# doorwatchV2.net
KiCad netlist of a schematic drawn in EAGLE
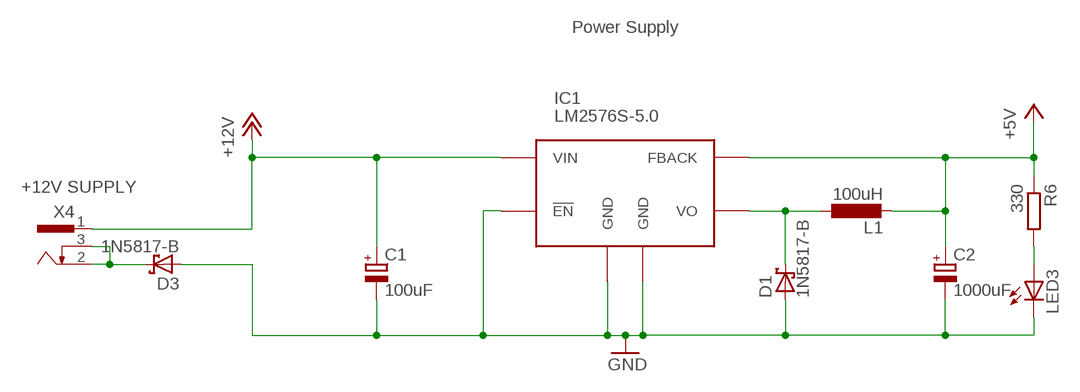
[diagram p0: schematic, sheet 1]
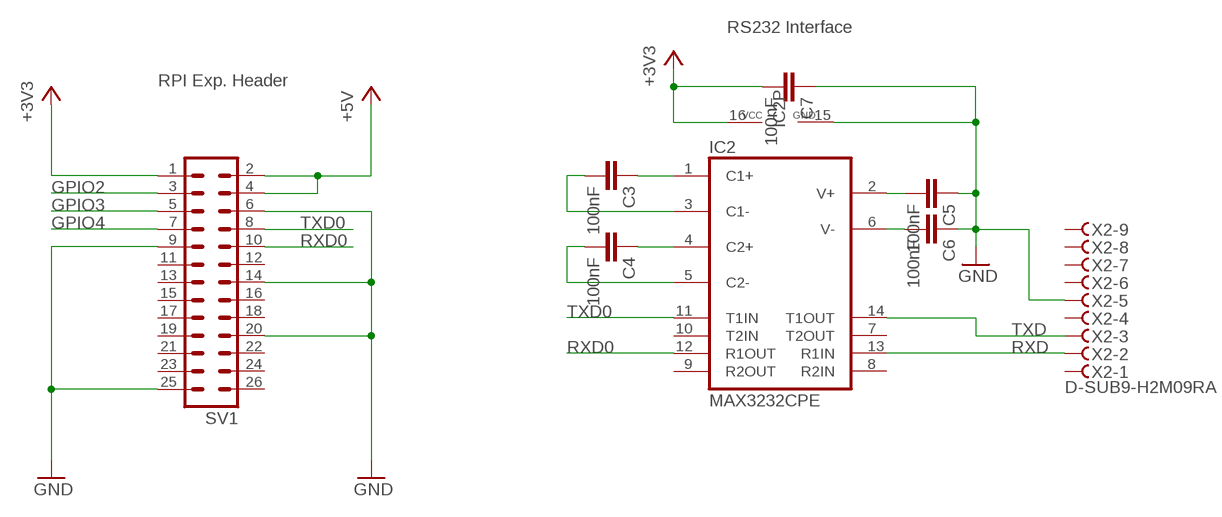
[diagram p1: schematic, sheet 2]
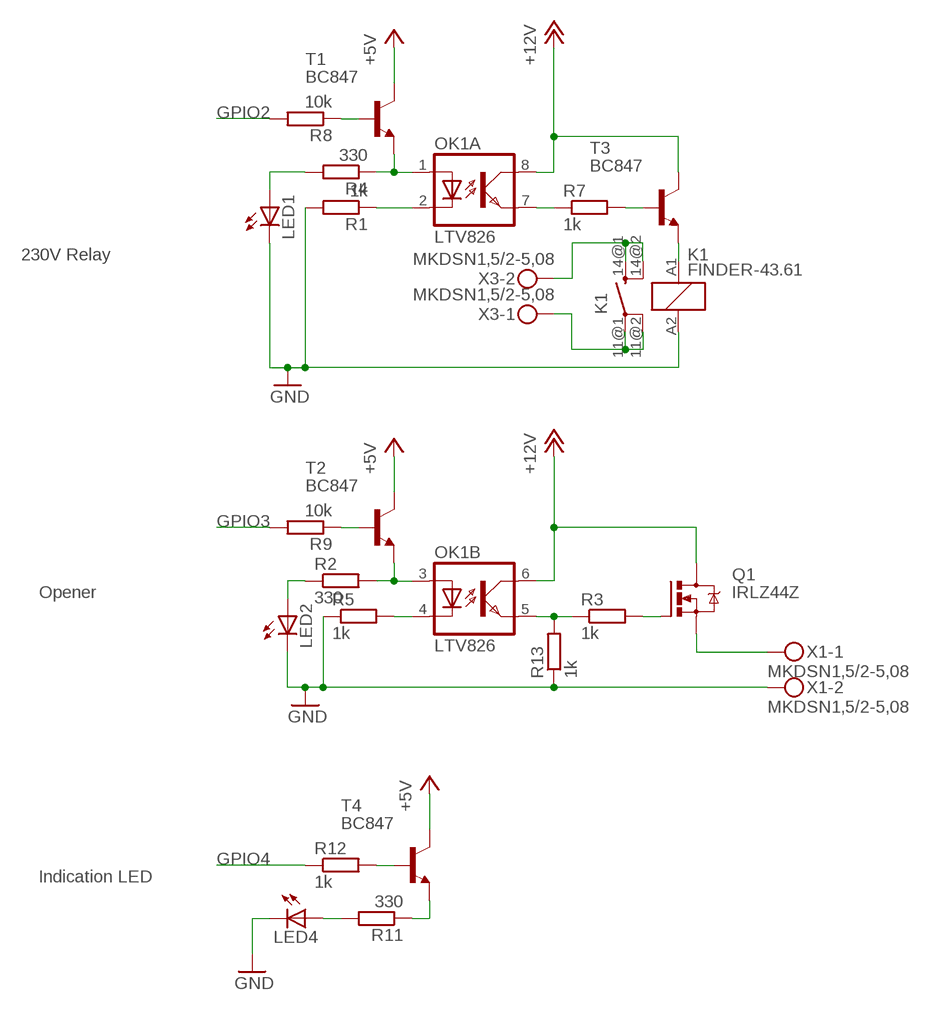
[diagram p2: schematic, sheet 3]
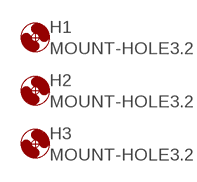
[diagram p3: schematic, sheet 4]

(export (version "E")
  (design (tool "Eeschema 10.0.6"))
  (components
    (comp (ref "H1")
      (value "MOUNT-HOLE3.2")
      (footprint "eagle-import:3,2")
      (libsource (lib "eagle-import") (part "MOUNT-HOLE3.2"))
    )
    (comp (ref "H2")
      (value "MOUNT-HOLE3.2")
      (footprint "eagle-import:3,2")
      (libsource (lib "eagle-import") (part "MOUNT-HOLE3.2"))
    )
    (comp (ref "H3")
      (value "MOUNT-HOLE3.2")
      (footprint "eagle-import:3,2")
      (libsource (lib "eagle-import") (part "MOUNT-HOLE3.2"))
    )
    (comp (ref "C1")
      (value "100uF")
      (footprint "eagle-import:E2,5-7")
      (libsource (lib "eagle-import") (part "CPOL-EUE2.5-7"))
    )
    (comp (ref "C2")
      (value "1000uF")
      (footprint "eagle-import:E5-10,5")
      (libsource (lib "eagle-import") (part "CPOL-EUE5-10.5"))
    )
    (comp (ref "D1")
      (value "1N5817-B")
      (footprint "eagle-import:DO41-7.6")
      (libsource (lib "eagle-import") (part "1N5817-B"))
    )
    (comp (ref "D3")
      (value "1N5817-B")
      (footprint "eagle-import:DO41-7.6")
      (libsource (lib "eagle-import") (part "1N5817-B"))
    )
    (comp (ref "IC1")
      (value "LM2576S-5.0")
      (footprint "eagle-import:TO263-5")
      (libsource (lib "eagle-import") (part "LM2576S"))
    )
    (comp (ref "L1")
      (value "100uH")
      (footprint "eagle-import:2200-20.32")
      (libsource (lib "eagle-import") (part "L-EU2200-20.32"))
    )
    (comp (ref "LED3")
      (value "LEDCHIP-LED0805")
      (footprint "eagle-import:CHIP-LED0805")
      (libsource (lib "eagle-import") (part "LEDCHIP-LED0805"))
    )
    (comp (ref "R6")
      (value "330")
      (footprint "eagle-import:M0805")
      (libsource (lib "eagle-import") (part "R-EU_M0805"))
    )
    (comp (ref "X4")
      (value "733980-62")
      (footprint "eagle-import:733980-62")
      (libsource (lib "eagle-import") (part "73398?0-62"))
    )
    (comp (ref "C3")
      (value "100nF")
      (footprint "eagle-import:C0805")
      (libsource (lib "eagle-import") (part "C-EUC0805"))
    )
    (comp (ref "C4")
      (value "100nF")
      (footprint "eagle-import:C0805")
      (libsource (lib "eagle-import") (part "C-EUC0805"))
    )
    (comp (ref "C5")
      (value "100nF")
      (footprint "eagle-import:C0805")
      (libsource (lib "eagle-import") (part "C-EUC0805"))
    )
    (comp (ref "C6")
      (value "100nF")
      (footprint "eagle-import:C0805")
      (libsource (lib "eagle-import") (part "C-EUC0805"))
    )
    (comp (ref "C7")
      (value "100nF")
      (footprint "eagle-import:C0805")
      (libsource (lib "eagle-import") (part "C-EUC0805"))
    )
    (comp (ref "IC2")
      (value "MAX3232CPE")
      (footprint "eagle-import:DIL16")
      (fields (field (name "MF") "MAXIM") (field (name "MPN") "MAX3232CPE+"))
      (libsource (lib "eagle-import") (part "MAX3232PEC"))
    )
    (comp (ref "SV1")
      (value "ML26")
      (footprint "eagle-import:ML26")
      (libsource (lib "eagle-import") (part "ML26"))
    )
    (comp (ref "X2")
      (value "D-SUB9-H2M09RA")
      (footprint "eagle-import:H2M09RA")
      (libsource (lib "eagle-import") (part "D-SUB9-H2M09RA"))
    )
    (comp (ref "K1")
      (value "FINDER-43.61")
      (footprint "eagle-import:FINDER-43.61")
      (libsource (lib "eagle-import") (part "FINDER-43.61"))
    )
    (comp (ref "LED1")
      (value "LEDCHIP-LED0805")
      (footprint "eagle-import:CHIP-LED0805")
      (libsource (lib "eagle-import") (part "LEDCHIP-LED0805"))
    )
    (comp (ref "LED2")
      (value "LEDCHIP-LED0805")
      (footprint "eagle-import:CHIP-LED0805")
      (libsource (lib "eagle-import") (part "LEDCHIP-LED0805"))
    )
    (comp (ref "LED4")
      (value "LEDCHIP-LED0805")
      (footprint "eagle-import:CHIP-LED0805")
      (libsource (lib "eagle-import") (part "LEDCHIP-LED0805"))
    )
    (comp (ref "OK1")
      (value "LTV826")
      (footprint "eagle-import:DIL08")
      (libsource (lib "eagle-import") (part "LTV826"))
    )
    (comp (ref "Q1")
      (value "IRLZ44Z")
      (footprint "eagle-import:TO220BH")
      (libsource (lib "eagle-import") (part "IRLZ44Z"))
    )
    (comp (ref "R1")
      (value "1k")
      (footprint "eagle-import:M0805")
      (libsource (lib "eagle-import") (part "R-EU_M0805"))
    )
    (comp (ref "R2")
      (value "330")
      (footprint "eagle-import:M0805")
      (libsource (lib "eagle-import") (part "R-EU_M0805"))
    )
    (comp (ref "R3")
      (value "1k")
      (footprint "eagle-import:M0805")
      (libsource (lib "eagle-import") (part "R-EU_M0805"))
    )
    (comp (ref "R4")
      (value "330")
      (footprint "eagle-import:M0805")
      (libsource (lib "eagle-import") (part "R-EU_M0805"))
    )
    (comp (ref "R5")
      (value "1k")
      (footprint "eagle-import:M0805")
      (libsource (lib "eagle-import") (part "R-EU_M0805"))
    )
    (comp (ref "R7")
      (value "1k")
      (footprint "eagle-import:M0805")
      (libsource (lib "eagle-import") (part "R-EU_M0805"))
    )
    (comp (ref "R8")
      (value "10k")
      (footprint "eagle-import:M0805")
      (libsource (lib "eagle-import") (part "R-EU_M0805"))
    )
    (comp (ref "R9")
      (value "10k")
      (footprint "eagle-import:M0805")
      (libsource (lib "eagle-import") (part "R-EU_M0805"))
    )
    (comp (ref "R11")
      (value "330")
      (footprint "eagle-import:M0805")
      (libsource (lib "eagle-import") (part "R-EU_M0805"))
    )
    (comp (ref "R12")
      (value "1k")
      (footprint "eagle-import:M0805")
      (libsource (lib "eagle-import") (part "R-EU_M0805"))
    )
    (comp (ref "R13")
      (value "1k")
      (footprint "eagle-import:M0805")
      (libsource (lib "eagle-import") (part "R-EU_M0805"))
    )
    (comp (ref "T1")
      (value "BC847")
      (footprint "eagle-import:SOT23")
      (libsource (lib "eagle-import") (part "BC847"))
    )
    (comp (ref "T2")
      (value "BC847")
      (footprint "eagle-import:SOT23")
      (libsource (lib "eagle-import") (part "BC847"))
    )
    (comp (ref "T3")
      (value "BC847")
      (footprint "eagle-import:SOT23")
      (libsource (lib "eagle-import") (part "BC847"))
    )
    (comp (ref "T4")
      (value "BC847")
      (footprint "eagle-import:SOT23")
      (libsource (lib "eagle-import") (part "BC847"))
    )
    (comp (ref "X1")
      (value "MKDSN1,5/2-5,08")
      (footprint "eagle-import:MKDSN1,5_2-5,08")
      (fields (field (name "MPN") "MKDSN 1,5/2-5.08"))
      (libsource (lib "eagle-import") (part "MKDSN1,5/2-5,08"))
    )
    (comp (ref "X3")
      (value "MKDSN1,5/2-5,08")
      (footprint "eagle-import:MKDSN1,5_2-5,08")
      (fields (field (name "MPN") "MKDSN 1,5/2-5.08"))
      (libsource (lib "eagle-import") (part "MKDSN1,5/2-5,08"))
    )
  )
  (nets
    (net (code "1") (name "+3V3") (class "Default")
      (node (ref "C7") (pin "2") (pinfunction "2_2") (pintype "passive"))
      (node (ref "IC2") (pin "16") (pinfunction "VCC_16") (pintype "power_in"))
      (node (ref "SV1") (pin "1") (pinfunction "1_1") (pintype "passive"))
    )
    (net (code "2") (name "+5V") (class "Default")
      (node (ref "C2") (pin "+") (pinfunction "+_+") (pintype "passive"))
      (node (ref "IC1") (pin "4") (pinfunction "FBACK_4") (pintype "bidirectional"))
      (node (ref "L1") (pin "2") (pinfunction "2_2") (pintype "passive"))
      (node (ref "R6") (pin "1") (pinfunction "1_1") (pintype "passive"))
      (node (ref "SV1") (pin "2") (pinfunction "2_2") (pintype "passive"))
      (node (ref "SV1") (pin "4") (pinfunction "4_4") (pintype "passive"))
      (node (ref "T1") (pin "3") (pinfunction "C_3") (pintype "passive"))
      (node (ref "T2") (pin "3") (pinfunction "C_3") (pintype "passive"))
      (node (ref "T4") (pin "3") (pinfunction "C_3") (pintype "passive"))
    )
    (net (code "3") (name "+12V") (class "Default")
      (node (ref "C1") (pin "+") (pinfunction "+_+") (pintype "passive"))
      (node (ref "IC1") (pin "1") (pinfunction "VIN_1") (pintype "bidirectional"))
      (node (ref "OK1") (pin "6") (pinfunction "COL_6") (pintype "passive"))
      (node (ref "OK1") (pin "8") (pinfunction "COL_8") (pintype "passive"))
      (node (ref "Q1") (pin "D") (pinfunction "D_D") (pintype "passive"))
      (node (ref "T3") (pin "3") (pinfunction "C_3") (pintype "passive"))
      (node (ref "X4") (pin "1") (pinfunction "1_1") (pintype "passive"))
    )
    (net (code "4") (name "GND") (class "Default")
      (node (ref "C1") (pin "-") (pinfunction "-_-") (pintype "passive"))
      (node (ref "C2") (pin "-") (pinfunction "-_-") (pintype "passive"))
      (node (ref "C5") (pin "1") (pinfunction "1_1") (pintype "passive"))
      (node (ref "C6") (pin "1") (pinfunction "1_1") (pintype "passive"))
      (node (ref "C7") (pin "1") (pinfunction "1_1") (pintype "passive"))
      (node (ref "D1") (pin "A") (pinfunction "A_A") (pintype "passive"))
      (node (ref "D3") (pin "A") (pinfunction "A_A") (pintype "passive"))
      (node (ref "IC1") (pin "3") (pinfunction "GND_3") (pintype "bidirectional"))
      (node (ref "IC1") (pin "5") (pinfunction "~{EN}_5") (pintype "bidirectional"))
      (node (ref "IC1") (pin "TAB") (pinfunction "GND_TAB") (pintype "bidirectional"))
      (node (ref "IC2") (pin "15") (pinfunction "GND_15") (pintype "power_in"))
      (node (ref "K1") (pin "A2") (pinfunction "2_A2") (pintype "passive"))
      (node (ref "LED1") (pin "C") (pinfunction "C_C") (pintype "passive"))
      (node (ref "LED2") (pin "C") (pinfunction "C_C") (pintype "passive"))
      (node (ref "LED3") (pin "C") (pinfunction "C_C") (pintype "passive"))
      (node (ref "LED4") (pin "C") (pinfunction "C_C") (pintype "passive"))
      (node (ref "R1") (pin "2") (pinfunction "2_2") (pintype "passive"))
      (node (ref "R13") (pin "1") (pinfunction "1_1") (pintype "passive"))
      (node (ref "R5") (pin "1") (pinfunction "1_1") (pintype "passive"))
      (node (ref "SV1") (pin "14") (pinfunction "14_14") (pintype "passive"))
      (node (ref "SV1") (pin "20") (pinfunction "20_20") (pintype "passive"))
      (node (ref "SV1") (pin "25") (pinfunction "25_25") (pintype "passive"))
      (node (ref "SV1") (pin "6") (pinfunction "6_6") (pintype "passive"))
      (node (ref "SV1") (pin "9") (pinfunction "9_9") (pintype "passive"))
      (node (ref "X1") (pin "2") (pinfunction "KL_2") (pintype "passive"))
      (node (ref "X2") (pin "5") (pinfunction "F_5") (pintype "passive"))
    )
    (net (code "5") (name "GPIO2") (class "Default")
      (node (ref "R8") (pin "2") (pinfunction "2_2") (pintype "passive"))
      (node (ref "SV1") (pin "3") (pinfunction "3_3") (pintype "passive"))
    )
    (net (code "6") (name "GPIO3") (class "Default")
      (node (ref "R9") (pin "2") (pinfunction "2_2") (pintype "passive"))
      (node (ref "SV1") (pin "5") (pinfunction "5_5") (pintype "passive"))
    )
    (net (code "7") (name "GPIO4") (class "Default")
      (node (ref "R12") (pin "1") (pinfunction "1_1") (pintype "passive"))
      (node (ref "SV1") (pin "7") (pinfunction "7_7") (pintype "passive"))
    )
    (net (code "8") (name "Net-(D3-PadC)") (class "Default")
      (node (ref "D3") (pin "C") (pinfunction "C_C") (pintype "passive"))
      (node (ref "X4") (pin "2") (pinfunction "2_2") (pintype "passive"))
      (node (ref "X4") (pin "3") (pinfunction "3_3") (pintype "passive"))
    )
    (net (code "9") (name "Net-(IC1-VO)") (class "Default")
      (node (ref "D1") (pin "C") (pinfunction "C_C") (pintype "passive"))
      (node (ref "IC1") (pin "2") (pinfunction "VO_2") (pintype "bidirectional"))
      (node (ref "L1") (pin "1") (pinfunction "1_1") (pintype "passive"))
    )
    (net (code "10") (name "Net-(IC2A-C1+)") (class "Default")
      (node (ref "C3") (pin "1") (pinfunction "1_1") (pintype "passive"))
      (node (ref "IC2") (pin "1") (pinfunction "C1+_1") (pintype "bidirectional"))
    )
    (net (code "11") (name "Net-(IC2A-C1-)") (class "Default")
      (node (ref "C3") (pin "2") (pinfunction "2_2") (pintype "passive"))
      (node (ref "IC2") (pin "3") (pinfunction "C1-_3") (pintype "bidirectional"))
    )
    (net (code "12") (name "Net-(IC2A-C2+)") (class "Default")
      (node (ref "C4") (pin "1") (pinfunction "1_1") (pintype "passive"))
      (node (ref "IC2") (pin "4") (pinfunction "C2+_4") (pintype "bidirectional"))
    )
    (net (code "13") (name "Net-(IC2A-C2-)") (class "Default")
      (node (ref "C4") (pin "2") (pinfunction "2_2") (pintype "passive"))
      (node (ref "IC2") (pin "5") (pinfunction "C2-_5") (pintype "bidirectional"))
    )
    (net (code "14") (name "Net-(IC2A-V+)") (class "Default")
      (node (ref "C5") (pin "2") (pinfunction "2_2") (pintype "passive"))
      (node (ref "IC2") (pin "2") (pinfunction "V+_2") (pintype "bidirectional"))
    )
    (net (code "15") (name "Net-(IC2A-V-)") (class "Default")
      (node (ref "C6") (pin "2") (pinfunction "2_2") (pintype "passive"))
      (node (ref "IC2") (pin "6") (pinfunction "V-_6") (pintype "bidirectional"))
    )
    (net (code "16") (name "Net-(K1A-PA)") (class "Default")
      (node (ref "K1") (pin "11@1") (pinfunction "PA_11@1") (pintype "passive"))
      (node (ref "K1") (pin "11@2") (pinfunction "PB_11@2") (pintype "passive"))
      (node (ref "X3") (pin "1") (pinfunction "KL_1") (pintype "passive"))
    )
    (net (code "17") (name "Net-(K1A-SA)") (class "Default")
      (node (ref "K1") (pin "14@1") (pinfunction "SA_14@1") (pintype "passive"))
      (node (ref "K1") (pin "14@2") (pinfunction "SB_14@2") (pintype "passive"))
      (node (ref "X3") (pin "2") (pinfunction "KL_2") (pintype "passive"))
    )
    (net (code "18") (name "Net-(K1B-1)") (class "Default")
      (node (ref "K1") (pin "A1") (pinfunction "1_A1") (pintype "passive"))
      (node (ref "T3") (pin "2") (pinfunction "E_2") (pintype "passive"))
    )
    (net (code "19") (name "Net-(LED1-PadA)") (class "Default")
      (node (ref "LED1") (pin "A") (pinfunction "A_A") (pintype "passive"))
      (node (ref "R4") (pin "2") (pinfunction "2_2") (pintype "passive"))
    )
    (net (code "20") (name "Net-(LED2-PadA)") (class "Default")
      (node (ref "LED2") (pin "A") (pinfunction "A_A") (pintype "passive"))
      (node (ref "R2") (pin "1") (pinfunction "1_1") (pintype "passive"))
    )
    (net (code "21") (name "Net-(LED3-PadA)") (class "Default")
      (node (ref "LED3") (pin "A") (pinfunction "A_A") (pintype "passive"))
      (node (ref "R6") (pin "2") (pinfunction "2_2") (pintype "passive"))
    )
    (net (code "22") (name "Net-(LED4-PadA)") (class "Default")
      (node (ref "LED4") (pin "A") (pinfunction "A_A") (pintype "passive"))
      (node (ref "R11") (pin "2") (pinfunction "2_2") (pintype "passive"))
    )
    (net (code "23") (name "Net-(OK1A-A)") (class "Default")
      (node (ref "OK1") (pin "1") (pinfunction "A_1") (pintype "passive"))
      (node (ref "R4") (pin "1") (pinfunction "1_1") (pintype "passive"))
      (node (ref "T1") (pin "2") (pinfunction "E_2") (pintype "passive"))
    )
    (net (code "24") (name "Net-(OK1A-C)") (class "Default")
      (node (ref "OK1") (pin "2") (pinfunction "C_2") (pintype "passive"))
      (node (ref "R1") (pin "1") (pinfunction "1_1") (pintype "passive"))
    )
    (net (code "25") (name "Net-(OK1A-EMIT)") (class "Default")
      (node (ref "OK1") (pin "7") (pinfunction "EMIT_7") (pintype "passive"))
      (node (ref "R7") (pin "1") (pinfunction "1_1") (pintype "passive"))
    )
    (net (code "26") (name "Net-(OK1B-A)") (class "Default")
      (node (ref "OK1") (pin "3") (pinfunction "A_3") (pintype "passive"))
      (node (ref "R2") (pin "2") (pinfunction "2_2") (pintype "passive"))
      (node (ref "T2") (pin "2") (pinfunction "E_2") (pintype "passive"))
    )
    (net (code "27") (name "Net-(OK1B-C)") (class "Default")
      (node (ref "OK1") (pin "4") (pinfunction "C_4") (pintype "passive"))
      (node (ref "R5") (pin "2") (pinfunction "2_2") (pintype "passive"))
    )
    (net (code "28") (name "Net-(OK1B-EMIT)") (class "Default")
      (node (ref "OK1") (pin "5") (pinfunction "EMIT_5") (pintype "passive"))
      (node (ref "R13") (pin "2") (pinfunction "2_2") (pintype "passive"))
      (node (ref "R3") (pin "1") (pinfunction "1_1") (pintype "passive"))
    )
    (net (code "29") (name "Net-(Q1-PadG)") (class "Default")
      (node (ref "Q1") (pin "G") (pinfunction "G_G") (pintype "passive"))
      (node (ref "R3") (pin "2") (pinfunction "2_2") (pintype "passive"))
    )
    (net (code "30") (name "Net-(T1-B)") (class "Default")
      (node (ref "R8") (pin "1") (pinfunction "1_1") (pintype "passive"))
      (node (ref "T1") (pin "1") (pinfunction "B_1") (pintype "passive"))
    )
    (net (code "31") (name "Net-(T2-B)") (class "Default")
      (node (ref "R9") (pin "1") (pinfunction "1_1") (pintype "passive"))
      (node (ref "T2") (pin "1") (pinfunction "B_1") (pintype "passive"))
    )
    (net (code "32") (name "Net-(T3-B)") (class "Default")
      (node (ref "R7") (pin "2") (pinfunction "2_2") (pintype "passive"))
      (node (ref "T3") (pin "1") (pinfunction "B_1") (pintype "passive"))
    )
    (net (code "33") (name "Net-(T4-B)") (class "Default")
      (node (ref "R12") (pin "2") (pinfunction "2_2") (pintype "passive"))
      (node (ref "T4") (pin "1") (pinfunction "B_1") (pintype "passive"))
    )
    (net (code "34") (name "Net-(T4-E)") (class "Default")
      (node (ref "R11") (pin "1") (pinfunction "1_1") (pintype "passive"))
      (node (ref "T4") (pin "2") (pinfunction "E_2") (pintype "passive"))
    )
    (net (code "35") (name "Net-(X1A-KL)") (class "Default")
      (node (ref "Q1") (pin "S") (pinfunction "S_S") (pintype "passive"))
      (node (ref "X1") (pin "1") (pinfunction "KL_1") (pintype "passive"))
    )
    (net (code "36") (name "RXD") (class "Default")
      (node (ref "IC2") (pin "13") (pinfunction "R1IN_13") (pintype "input"))
      (node (ref "X2") (pin "2") (pinfunction "F_2") (pintype "passive"))
    )
    (net (code "37") (name "RXD0") (class "Default")
      (node (ref "IC2") (pin "12") (pinfunction "R1OUT_12") (pintype "output"))
      (node (ref "SV1") (pin "10") (pinfunction "10_10") (pintype "passive"))
    )
    (net (code "38") (name "TXD") (class "Default")
      (node (ref "IC2") (pin "14") (pinfunction "T1OUT_14") (pintype "output"))
      (node (ref "X2") (pin "3") (pinfunction "F_3") (pintype "passive"))
    )
    (net (code "39") (name "TXD0") (class "Default")
      (node (ref "IC2") (pin "11") (pinfunction "T1IN_11") (pintype "input"))
      (node (ref "SV1") (pin "8") (pinfunction "8_8") (pintype "passive"))
    )
    (net (code "40") (name "unconnected-(IC2A-R2IN-Pad8)") (class "Default")
      (node (ref "IC2") (pin "8") (pinfunction "R2IN_8") (pintype "input"))
    )
    (net (code "41") (name "unconnected-(IC2A-R2OUT-Pad9)") (class "Default")
      (node (ref "IC2") (pin "9") (pinfunction "R2OUT_9") (pintype "output"))
    )
    (net (code "42") (name "unconnected-(IC2A-T2IN-Pad10)") (class "Default")
      (node (ref "IC2") (pin "10") (pinfunction "T2IN_10") (pintype "input"))
    )
    (net (code "43") (name "unconnected-(IC2A-T2OUT-Pad7)") (class "Default")
      (node (ref "IC2") (pin "7") (pinfunction "T2OUT_7") (pintype "output"))
    )
    (net (code "44") (name "unconnected-(SV1-Pad11)") (class "Default")
      (node (ref "SV1") (pin "11") (pinfunction "11_11") (pintype "passive"))
    )
    (net (code "45") (name "unconnected-(SV1-Pad12)") (class "Default")
      (node (ref "SV1") (pin "12") (pinfunction "12_12") (pintype "passive"))
    )
    (net (code "46") (name "unconnected-(SV1-Pad13)") (class "Default")
      (node (ref "SV1") (pin "13") (pinfunction "13_13") (pintype "passive"))
    )
    (net (code "47") (name "unconnected-(SV1-Pad15)") (class "Default")
      (node (ref "SV1") (pin "15") (pinfunction "15_15") (pintype "passive"))
    )
    (net (code "48") (name "unconnected-(SV1-Pad16)") (class "Default")
      (node (ref "SV1") (pin "16") (pinfunction "16_16") (pintype "passive"))
    )
    (net (code "49") (name "unconnected-(SV1-Pad17)") (class "Default")
      (node (ref "SV1") (pin "17") (pinfunction "17_17") (pintype "passive"))
    )
    (net (code "50") (name "unconnected-(SV1-Pad18)") (class "Default")
      (node (ref "SV1") (pin "18") (pinfunction "18_18") (pintype "passive"))
    )
    (net (code "51") (name "unconnected-(SV1-Pad19)") (class "Default")
      (node (ref "SV1") (pin "19") (pinfunction "19_19") (pintype "passive"))
    )
    (net (code "52") (name "unconnected-(SV1-Pad21)") (class "Default")
      (node (ref "SV1") (pin "21") (pinfunction "21_21") (pintype "passive"))
    )
    (net (code "53") (name "unconnected-(SV1-Pad22)") (class "Default")
      (node (ref "SV1") (pin "22") (pinfunction "22_22") (pintype "passive"))
    )
    (net (code "54") (name "unconnected-(SV1-Pad23)") (class "Default")
      (node (ref "SV1") (pin "23") (pinfunction "23_23") (pintype "passive"))
    )
    (net (code "55") (name "unconnected-(SV1-Pad24)") (class "Default")
      (node (ref "SV1") (pin "24") (pinfunction "24_24") (pintype "passive"))
    )
    (net (code "56") (name "unconnected-(SV1-Pad26)") (class "Default")
      (node (ref "SV1") (pin "26") (pinfunction "26_26") (pintype "passive"))
    )
    (net (code "57") (name "unconnected-(X2A-F-Pad1)") (class "Default")
      (node (ref "X2") (pin "1") (pinfunction "F_1") (pintype "passive"))
    )
    (net (code "58") (name "unconnected-(X2D-F-Pad4)") (class "Default")
      (node (ref "X2") (pin "4") (pinfunction "F_4") (pintype "passive"))
    )
    (net (code "59") (name "unconnected-(X2F-F-Pad6)") (class "Default")
      (node (ref "X2") (pin "6") (pinfunction "F_6") (pintype "passive"))
    )
    (net (code "60") (name "unconnected-(X2G-F-Pad7)") (class "Default")
      (node (ref "X2") (pin "7") (pinfunction "F_7") (pintype "passive"))
    )
    (net (code "61") (name "unconnected-(X2H-F-Pad8)") (class "Default")
      (node (ref "X2") (pin "8") (pinfunction "F_8") (pintype "passive"))
    )
    (net (code "62") (name "unconnected-(X2I-F-Pad9)") (class "Default")
      (node (ref "X2") (pin "9") (pinfunction "F_9") (pintype "passive"))
    )
  )
)
